# grissom.net
KiCad netlist of a schematic drawn in EAGLE
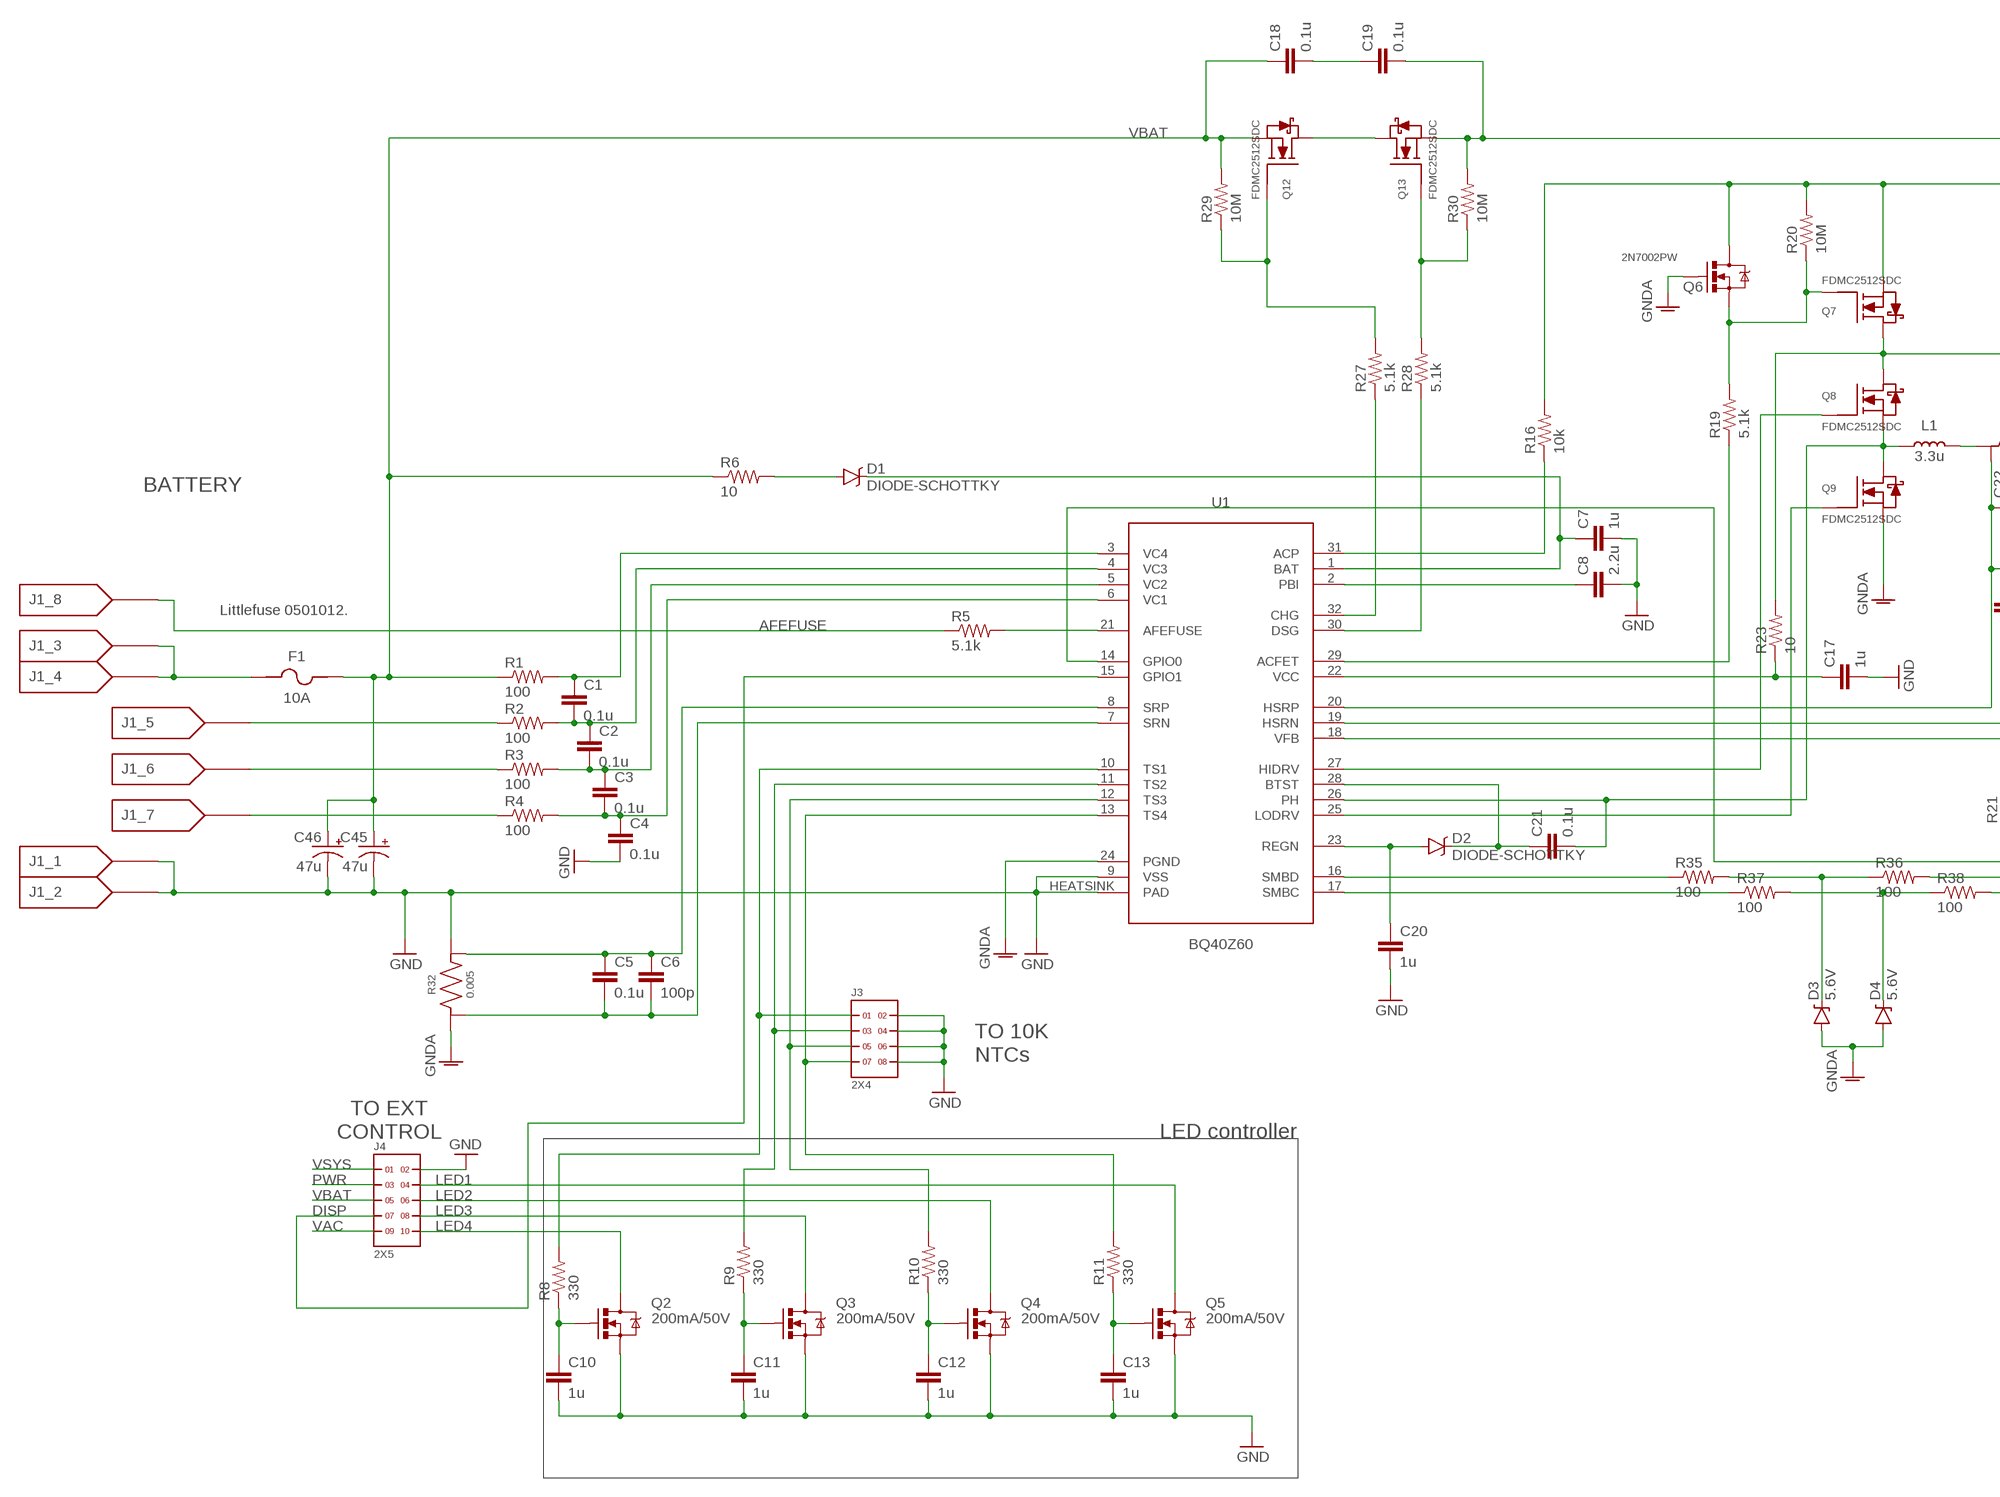
[diagram p0: schematic, sheet 1, part 1 of 2]
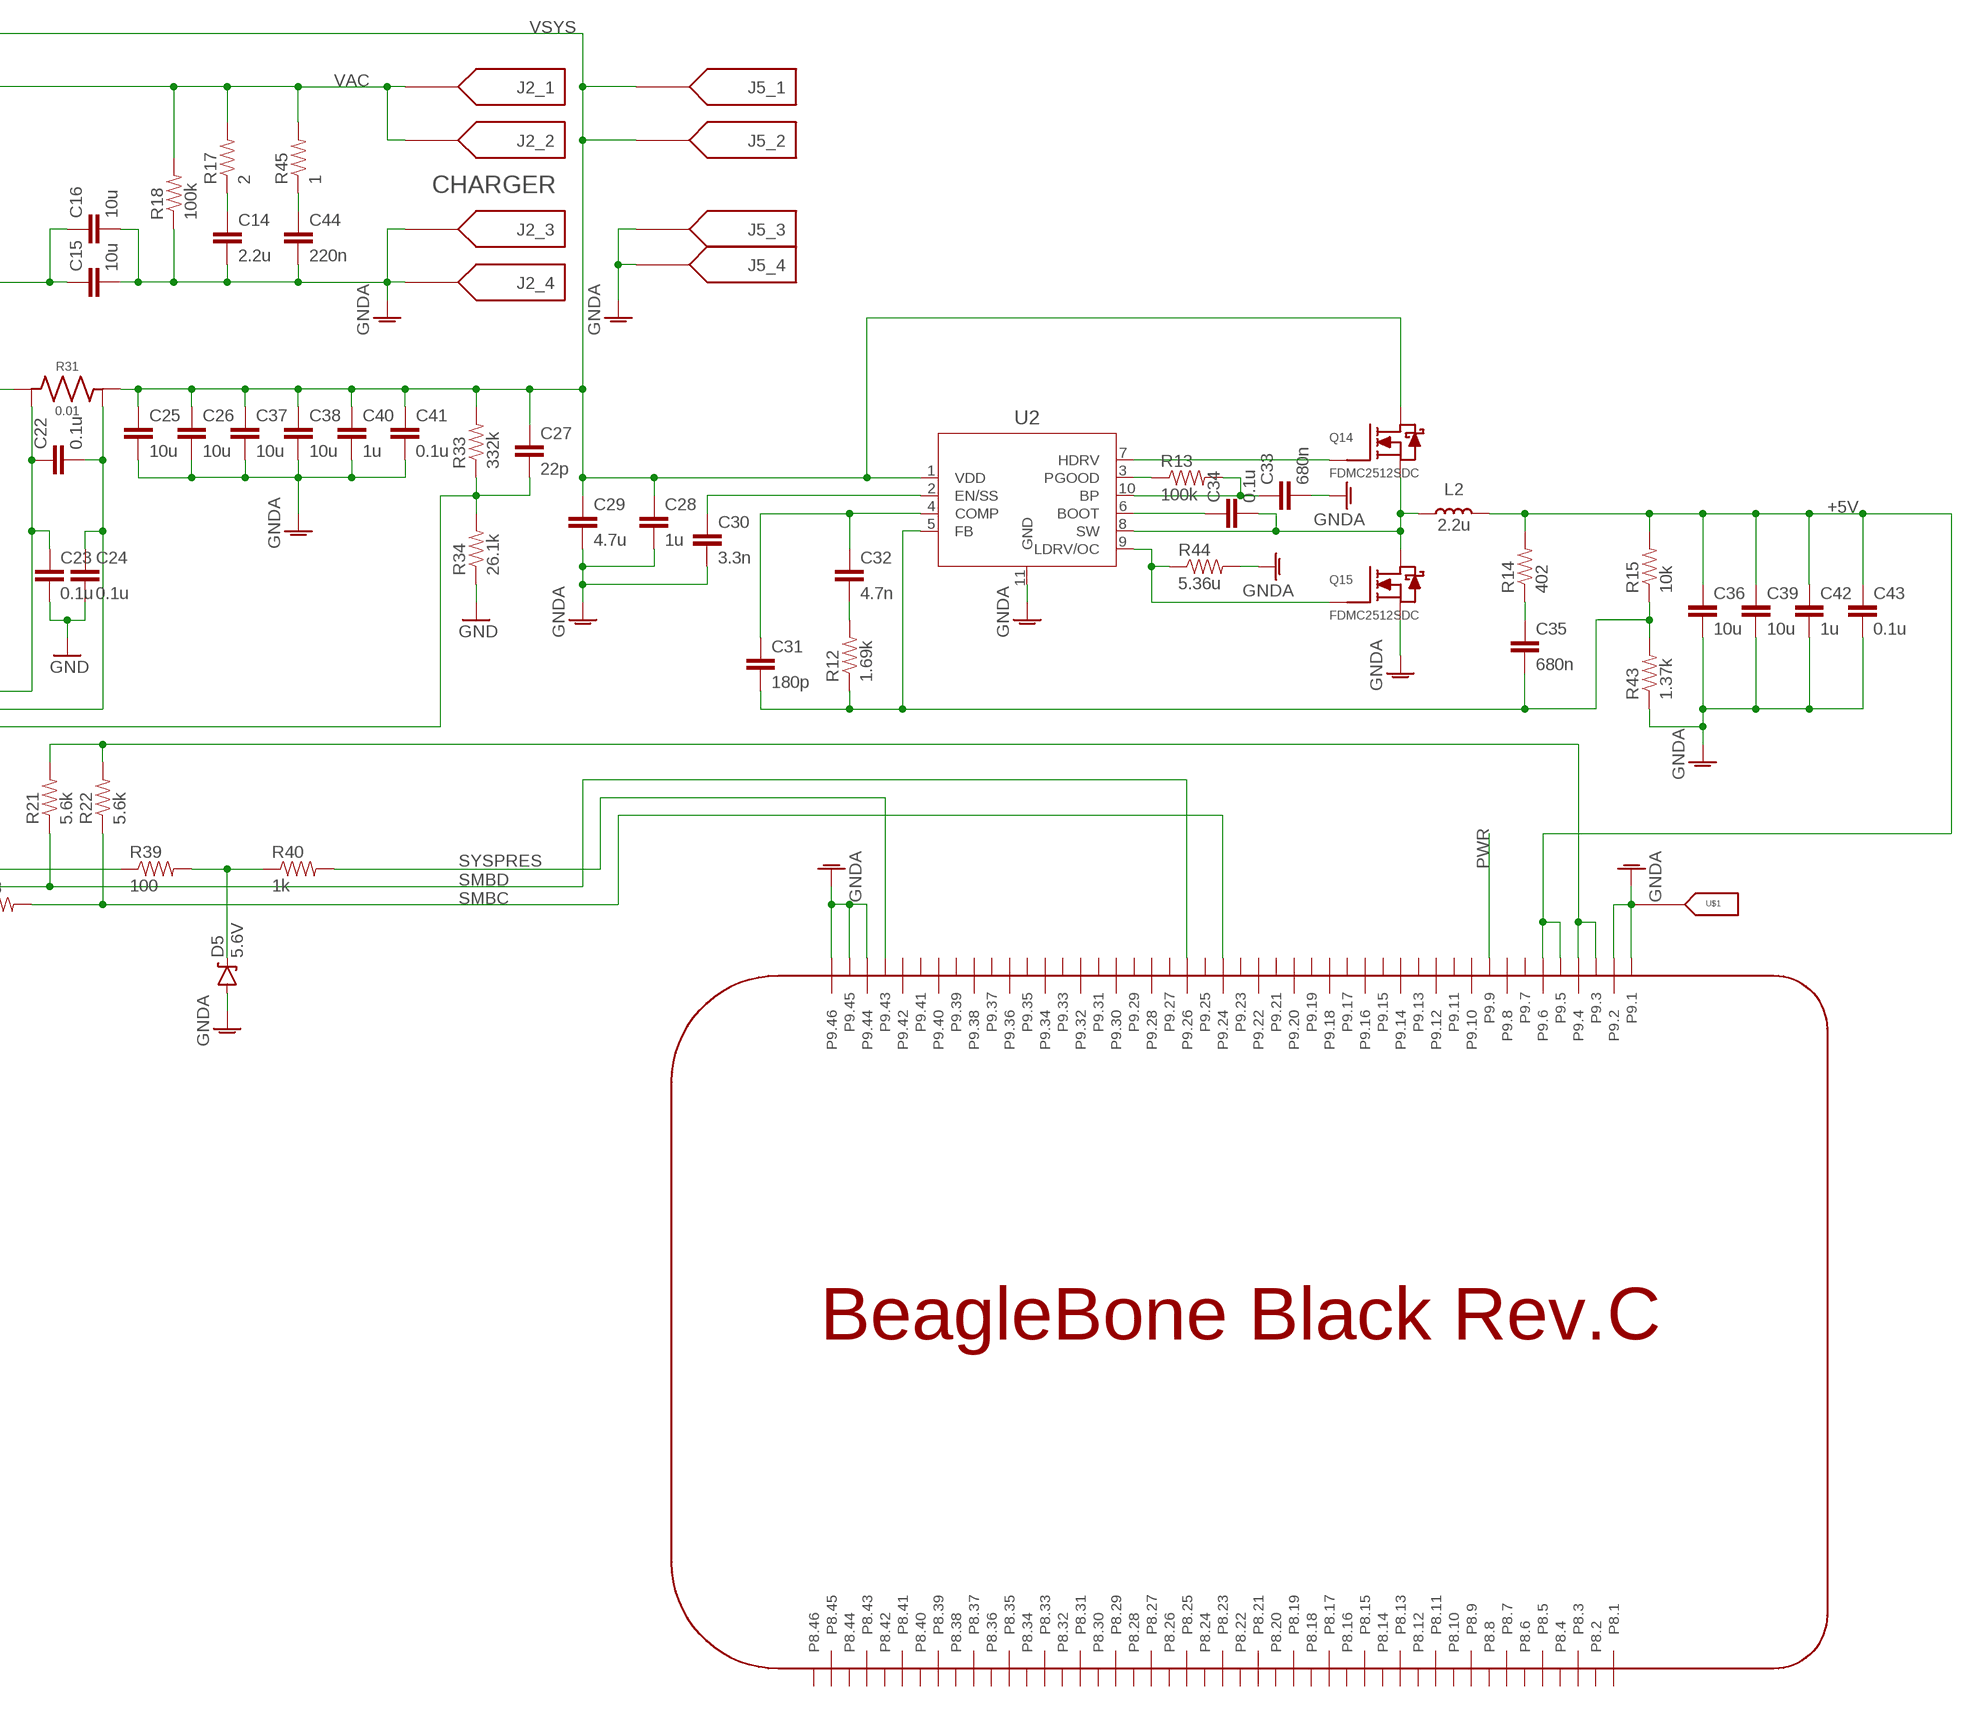
[diagram p1: schematic, sheet 1, part 2 of 2]

(export (version "E")
  (design (tool "Eeschema 10.0.6"))
  (components
    (comp (ref "C1")
      (value "0.1u")
      (footprint "eagle-import:0805")
      (libsource (lib "eagle-import") (part "CAP0805"))
    )
    (comp (ref "C2")
      (value "0.1u")
      (footprint "eagle-import:0805")
      (libsource (lib "eagle-import") (part "CAP0805"))
    )
    (comp (ref "C3")
      (value "0.1u")
      (footprint "eagle-import:0805")
      (libsource (lib "eagle-import") (part "CAP0805"))
    )
    (comp (ref "C4")
      (value "0.1u")
      (footprint "eagle-import:0805")
      (libsource (lib "eagle-import") (part "CAP0805"))
    )
    (comp (ref "C5")
      (value "0.1u")
      (footprint "eagle-import:0805")
      (libsource (lib "eagle-import") (part "CAP0805"))
    )
    (comp (ref "C6")
      (value "100p")
      (footprint "eagle-import:0805")
      (libsource (lib "eagle-import") (part "CAP0805"))
    )
    (comp (ref "C7")
      (value "1u")
      (footprint "eagle-import:0805")
      (libsource (lib "eagle-import") (part "CAP0805"))
    )
    (comp (ref "C8")
      (value "2.2u")
      (footprint "eagle-import:0805")
      (libsource (lib "eagle-import") (part "CAP0805"))
    )
    (comp (ref "C10")
      (value "1u")
      (footprint "eagle-import:0805")
      (libsource (lib "eagle-import") (part "CAP0805"))
    )
    (comp (ref "C11")
      (value "1u")
      (footprint "eagle-import:0805")
      (libsource (lib "eagle-import") (part "CAP0805"))
    )
    (comp (ref "C12")
      (value "1u")
      (footprint "eagle-import:0805")
      (libsource (lib "eagle-import") (part "CAP0805"))
    )
    (comp (ref "C13")
      (value "1u")
      (footprint "eagle-import:0805")
      (libsource (lib "eagle-import") (part "CAP0805"))
    )
    (comp (ref "C14")
      (value "2.2u")
      (footprint "eagle-import:0805")
      (libsource (lib "eagle-import") (part "CAP0805"))
    )
    (comp (ref "C15")
      (value "10u")
      (footprint "eagle-import:1206")
      (libsource (lib "eagle-import") (part "CAP1206"))
    )
    (comp (ref "C16")
      (value "10u")
      (footprint "eagle-import:1206")
      (libsource (lib "eagle-import") (part "CAP1206"))
    )
    (comp (ref "C17")
      (value "1u")
      (footprint "eagle-import:0805")
      (libsource (lib "eagle-import") (part "CAP0805"))
    )
    (comp (ref "C18")
      (value "0.1u")
      (footprint "eagle-import:0805")
      (libsource (lib "eagle-import") (part "CAP0805"))
    )
    (comp (ref "C19")
      (value "0.1u")
      (footprint "eagle-import:0805")
      (libsource (lib "eagle-import") (part "CAP0805"))
    )
    (comp (ref "C20")
      (value "1u")
      (footprint "eagle-import:0805")
      (libsource (lib "eagle-import") (part "CAP0805"))
    )
    (comp (ref "C21")
      (value "0.1u")
      (footprint "eagle-import:0805")
      (libsource (lib "eagle-import") (part "CAP0805"))
    )
    (comp (ref "C22")
      (value "0.1u")
      (footprint "eagle-import:0805")
      (libsource (lib "eagle-import") (part "CAP0805"))
    )
    (comp (ref "C23")
      (value "0.1u")
      (footprint "eagle-import:0805")
      (libsource (lib "eagle-import") (part "CAP0805"))
    )
    (comp (ref "C24")
      (value "0.1u")
      (footprint "eagle-import:0805")
      (libsource (lib "eagle-import") (part "CAP0805"))
    )
    (comp (ref "C25")
      (value "10u")
      (footprint "eagle-import:1206")
      (libsource (lib "eagle-import") (part "CAP1206"))
    )
    (comp (ref "C26")
      (value "10u")
      (footprint "eagle-import:1206")
      (libsource (lib "eagle-import") (part "CAP1206"))
    )
    (comp (ref "C27")
      (value "22p")
      (footprint "eagle-import:0805")
      (libsource (lib "eagle-import") (part "CAP0805"))
    )
    (comp (ref "C28")
      (value "1u")
      (footprint "eagle-import:0805")
      (libsource (lib "eagle-import") (part "CAP0805"))
    )
    (comp (ref "C29")
      (value "4.7u")
      (footprint "eagle-import:0805")
      (libsource (lib "eagle-import") (part "CAP0805"))
    )
    (comp (ref "C30")
      (value "3.3n")
      (footprint "eagle-import:0805")
      (libsource (lib "eagle-import") (part "CAP0805"))
    )
    (comp (ref "C31")
      (value "180p")
      (footprint "eagle-import:0805")
      (libsource (lib "eagle-import") (part "CAP0805"))
    )
    (comp (ref "C32")
      (value "4.7n")
      (footprint "eagle-import:0805")
      (libsource (lib "eagle-import") (part "CAP0805"))
    )
    (comp (ref "C33")
      (value "680n")
      (footprint "eagle-import:0805")
      (libsource (lib "eagle-import") (part "CAP0805"))
    )
    (comp (ref "C34")
      (value "0.1u")
      (footprint "eagle-import:0805")
      (libsource (lib "eagle-import") (part "CAP0805"))
    )
    (comp (ref "C35")
      (value "680n")
      (footprint "eagle-import:0805")
      (libsource (lib "eagle-import") (part "CAP0805"))
    )
    (comp (ref "C36")
      (value "10u")
      (footprint "eagle-import:1206")
      (libsource (lib "eagle-import") (part "CAP1206"))
    )
    (comp (ref "C37")
      (value "10u")
      (footprint "eagle-import:1206")
      (libsource (lib "eagle-import") (part "CAP1206"))
    )
    (comp (ref "C38")
      (value "10u")
      (footprint "eagle-import:1206")
      (libsource (lib "eagle-import") (part "CAP1206"))
    )
    (comp (ref "C39")
      (value "10u")
      (footprint "eagle-import:1206")
      (libsource (lib "eagle-import") (part "CAP1206"))
    )
    (comp (ref "C40")
      (value "1u")
      (footprint "eagle-import:1206")
      (libsource (lib "eagle-import") (part "CAP1206"))
    )
    (comp (ref "C41")
      (value "0.1u")
      (footprint "eagle-import:1206")
      (libsource (lib "eagle-import") (part "CAP1206"))
    )
    (comp (ref "C42")
      (value "1u")
      (footprint "eagle-import:1206")
      (libsource (lib "eagle-import") (part "CAP1206"))
    )
    (comp (ref "C43")
      (value "0.1u")
      (footprint "eagle-import:1206")
      (libsource (lib "eagle-import") (part "CAP1206"))
    )
    (comp (ref "C44")
      (value "220n")
      (footprint "eagle-import:0805")
      (libsource (lib "eagle-import") (part "CAP0805"))
    )
    (comp (ref "C45")
      (value "47u")
      (footprint "eagle-import:CPOL-RADIAL-10UF-25V")
      (libsource (lib "eagle-import") (part "CAP_POLPTH2"))
    )
    (comp (ref "C46")
      (value "47u")
      (footprint "eagle-import:CPOL-RADIAL-10UF-25V")
      (libsource (lib "eagle-import") (part "CAP_POLPTH2"))
    )
    (comp (ref "D1")
      (value "DIODE-SCHOTTKY")
      (footprint "eagle-import:SOT23-3")
      (libsource (lib "eagle-import") (part "DIODE-SCHOTTKY"))
    )
    (comp (ref "D2")
      (value "DIODE-SCHOTTKY")
      (footprint "eagle-import:SOT23-3")
      (libsource (lib "eagle-import") (part "DIODE-SCHOTTKY"))
    )
    (comp (ref "D3")
      (value "5.6V")
      (footprint "eagle-import:SOD-323")
      (libsource (lib "eagle-import") (part "DIODE-ZENER5.6V"))
    )
    (comp (ref "D4")
      (value "5.6V")
      (footprint "eagle-import:SOD-323")
      (libsource (lib "eagle-import") (part "DIODE-ZENER5.6V"))
    )
    (comp (ref "D5")
      (value "5.6V")
      (footprint "eagle-import:SOD-323")
      (libsource (lib "eagle-import") (part "DIODE-ZENER5.6V"))
    )
    (comp (ref "F1")
      (value "10A")
      (footprint "eagle-import:LITTELFUSE_501")
      (libsource (lib "eagle-import") (part "LITTELFUSE_501"))
    )
    (comp (ref "J1")
      (value "105314-X208")
      (footprint "eagle-import:105314-X208")
      (libsource (lib "eagle-import") (part "105314-X208"))
    )
    (comp (ref "J2")
      (value "105314-X204")
      (footprint "eagle-import:105314-X204")
      (libsource (lib "eagle-import") (part "105314-X204"))
    )
    (comp (ref "J3")
      (value "2X4")
      (footprint "eagle-import:2X4")
      (libsource (lib "eagle-import") (part "2X4"))
    )
    (comp (ref "J4")
      (value "2X5")
      (footprint "eagle-import:2X5")
      (libsource (lib "eagle-import") (part "2X5"))
    )
    (comp (ref "J5")
      (value "105314-X204")
      (footprint "eagle-import:105314-X204")
      (libsource (lib "eagle-import") (part "105314-X204"))
    )
    (comp (ref "L1")
      (value "3.3u")
      (footprint "eagle-import:BOURNS_SRP7028A")
      (libsource (lib "eagle-import") (part "BOURNS_SRP7028A"))
    )
    (comp (ref "L2")
      (value "2.2u")
      (footprint "eagle-import:BOURNS_SRP7028A")
      (libsource (lib "eagle-import") (part "BOURNS_SRP7028A"))
    )
    (comp (ref "PCB1")
      (value "BEAGLEBONE_BLACK_BLANK")
      (footprint "eagle-import:BEAGLEBONE_BLACK_BLANK")
      (libsource (lib "eagle-import") (part "BEAGLEBONE_BLACK_BLANK"))
    )
    (comp (ref "Q2")
      (value "200mA/50V")
      (footprint "eagle-import:SOT23-3")
      (libsource (lib "eagle-import") (part "MOSFET-NCHANNELBSS138"))
    )
    (comp (ref "Q3")
      (value "200mA/50V")
      (footprint "eagle-import:SOT23-3")
      (libsource (lib "eagle-import") (part "MOSFET-NCHANNELBSS138"))
    )
    (comp (ref "Q4")
      (value "200mA/50V")
      (footprint "eagle-import:SOT23-3")
      (libsource (lib "eagle-import") (part "MOSFET-NCHANNELBSS138"))
    )
    (comp (ref "Q5")
      (value "200mA/50V")
      (footprint "eagle-import:SOT23-3")
      (libsource (lib "eagle-import") (part "MOSFET-NCHANNELBSS138"))
    )
    (comp (ref "Q6")
      (value "2N7002PW")
      (footprint "eagle-import:SOT323")
      (libsource (lib "eagle-import") (part "MOSFET-NCHANNEL2N7002PW"))
    )
    (comp (ref "Q7")
      (value "FDMC2512SDC")
      (footprint "eagle-import:MO240")
      (libsource (lib "eagle-import") (part "FDMC2512SDC"))
    )
    (comp (ref "Q8")
      (value "FDMC2512SDC")
      (footprint "eagle-import:MO240")
      (libsource (lib "eagle-import") (part "FDMC2512SDC"))
    )
    (comp (ref "Q9")
      (value "FDMC2512SDC")
      (footprint "eagle-import:MO240")
      (libsource (lib "eagle-import") (part "FDMC2512SDC"))
    )
    (comp (ref "Q12")
      (value "FDMC2512SDC")
      (footprint "eagle-import:MO240")
      (libsource (lib "eagle-import") (part "FDMC2512SDC"))
    )
    (comp (ref "Q13")
      (value "FDMC2512SDC")
      (footprint "eagle-import:MO240")
      (libsource (lib "eagle-import") (part "FDMC2512SDC"))
    )
    (comp (ref "Q14")
      (value "FDMC2512SDC")
      (footprint "eagle-import:MO240")
      (libsource (lib "eagle-import") (part "FDMC2512SDC"))
    )
    (comp (ref "Q15")
      (value "FDMC2512SDC")
      (footprint "eagle-import:MO240")
      (libsource (lib "eagle-import") (part "FDMC2512SDC"))
    )
    (comp (ref "R1")
      (value "100")
      (footprint "eagle-import:0805")
      (libsource (lib "eagle-import") (part "RESISTOR0805-RES"))
    )
    (comp (ref "R2")
      (value "100")
      (footprint "eagle-import:0805")
      (libsource (lib "eagle-import") (part "RESISTOR0805-RES"))
    )
    (comp (ref "R3")
      (value "100")
      (footprint "eagle-import:0805")
      (libsource (lib "eagle-import") (part "RESISTOR0805-RES"))
    )
    (comp (ref "R4")
      (value "100")
      (footprint "eagle-import:0805")
      (libsource (lib "eagle-import") (part "RESISTOR0805-RES"))
    )
    (comp (ref "R5")
      (value "5.1k")
      (footprint "eagle-import:0805")
      (libsource (lib "eagle-import") (part "RESISTOR0805-RES"))
    )
    (comp (ref "R6")
      (value "10")
      (footprint "eagle-import:1206")
      (libsource (lib "eagle-import") (part "RESISTOR1206"))
    )
    (comp (ref "R8")
      (value "330")
      (footprint "eagle-import:0805")
      (libsource (lib "eagle-import") (part "RESISTOR0805-RES"))
    )
    (comp (ref "R9")
      (value "330")
      (footprint "eagle-import:0805")
      (libsource (lib "eagle-import") (part "RESISTOR0805-RES"))
    )
    (comp (ref "R10")
      (value "330")
      (footprint "eagle-import:0805")
      (libsource (lib "eagle-import") (part "RESISTOR0805-RES"))
    )
    (comp (ref "R11")
      (value "330")
      (footprint "eagle-import:0805")
      (libsource (lib "eagle-import") (part "RESISTOR0805-RES"))
    )
    (comp (ref "R12")
      (value "1.69k")
      (footprint "eagle-import:0805")
      (libsource (lib "eagle-import") (part "RESISTOR0805-RES"))
    )
    (comp (ref "R13")
      (value "100k")
      (footprint "eagle-import:0805")
      (libsource (lib "eagle-import") (part "RESISTOR0805-RES"))
    )
    (comp (ref "R14")
      (value "402")
      (footprint "eagle-import:0805")
      (libsource (lib "eagle-import") (part "RESISTOR0805-RES"))
    )
    (comp (ref "R15")
      (value "10k")
      (footprint "eagle-import:0805")
      (libsource (lib "eagle-import") (part "RESISTOR0805-RES"))
    )
    (comp (ref "R16")
      (value "10k")
      (footprint "eagle-import:0805")
      (libsource (lib "eagle-import") (part "RESISTOR0805-RES"))
    )
    (comp (ref "R17")
      (value "2")
      (footprint "eagle-import:0805")
      (libsource (lib "eagle-import") (part "RESISTOR0805-RES"))
    )
    (comp (ref "R18")
      (value "100k")
      (footprint "eagle-import:0805")
      (libsource (lib "eagle-import") (part "RESISTOR0805-RES"))
    )
    (comp (ref "R19")
      (value "5.1k")
      (footprint "eagle-import:0805")
      (libsource (lib "eagle-import") (part "RESISTOR0805-RES"))
    )
    (comp (ref "R20")
      (value "10M")
      (footprint "eagle-import:0805")
      (libsource (lib "eagle-import") (part "RESISTOR0805-RES"))
    )
    (comp (ref "R21")
      (value "5.6k")
      (footprint "eagle-import:0805")
      (libsource (lib "eagle-import") (part "RESISTOR0805-RES"))
    )
    (comp (ref "R22")
      (value "5.6k")
      (footprint "eagle-import:0805")
      (libsource (lib "eagle-import") (part "RESISTOR0805-RES"))
    )
    (comp (ref "R23")
      (value "10")
      (footprint "eagle-import:0805")
      (libsource (lib "eagle-import") (part "RESISTOR0805-RES"))
    )
    (comp (ref "R27")
      (value "5.1k")
      (footprint "eagle-import:0805")
      (libsource (lib "eagle-import") (part "RESISTOR0805-RES"))
    )
    (comp (ref "R28")
      (value "5.1k")
      (footprint "eagle-import:0805")
      (libsource (lib "eagle-import") (part "RESISTOR0805-RES"))
    )
    (comp (ref "R29")
      (value "10M")
      (footprint "eagle-import:0805")
      (libsource (lib "eagle-import") (part "RESISTOR0805-RES"))
    )
    (comp (ref "R30")
      (value "10M")
      (footprint "eagle-import:0805")
      (libsource (lib "eagle-import") (part "RESISTOR0805-RES"))
    )
    (comp (ref "R31")
      (value "0.01")
      (footprint "eagle-import:1206_4T")
      (libsource (lib "eagle-import") (part "OHMITE_FC4L32"))
    )
    (comp (ref "R32")
      (value "0.005")
      (footprint "eagle-import:0612_4T")
      (libsource (lib "eagle-import") (part "VISHAY_WSK0612"))
    )
    (comp (ref "R33")
      (value "332k")
      (footprint "eagle-import:0805")
      (libsource (lib "eagle-import") (part "RESISTOR0805-RES"))
    )
    (comp (ref "R34")
      (value "26.1k")
      (footprint "eagle-import:0805")
      (libsource (lib "eagle-import") (part "RESISTOR0805-RES"))
    )
    (comp (ref "R35")
      (value "100")
      (footprint "eagle-import:0805")
      (libsource (lib "eagle-import") (part "RESISTOR0805-RES"))
    )
    (comp (ref "R36")
      (value "100")
      (footprint "eagle-import:0805")
      (libsource (lib "eagle-import") (part "RESISTOR0805-RES"))
    )
    (comp (ref "R37")
      (value "100")
      (footprint "eagle-import:0805")
      (libsource (lib "eagle-import") (part "RESISTOR0805-RES"))
    )
    (comp (ref "R38")
      (value "100")
      (footprint "eagle-import:0805")
      (libsource (lib "eagle-import") (part "RESISTOR0805-RES"))
    )
    (comp (ref "R39")
      (value "100")
      (footprint "eagle-import:0805")
      (libsource (lib "eagle-import") (part "RESISTOR0805-RES"))
    )
    (comp (ref "R40")
      (value "1k")
      (footprint "eagle-import:0805")
      (libsource (lib "eagle-import") (part "RESISTOR0805-RES"))
    )
    (comp (ref "R43")
      (value "1.37k")
      (footprint "eagle-import:0805")
      (libsource (lib "eagle-import") (part "RESISTOR0805-RES"))
    )
    (comp (ref "R44")
      (value "5.36u")
      (footprint "eagle-import:0805")
      (libsource (lib "eagle-import") (part "RESISTOR0805-RES"))
    )
    (comp (ref "R45")
      (value "1")
      (footprint "eagle-import:0805")
      (libsource (lib "eagle-import") (part "RESISTOR0805-RES"))
    )
    (comp (ref "U$1")
      (value "SU_LOGO-DUMMY2")
      (footprint "eagle-import:SU_LOGO_SS")
      (libsource (lib "eagle-import") (part "SU_LOGO-DUMMY2"))
    )
    (comp (ref "U1")
      (value "BQ40Z60")
      (footprint "eagle-import:QFN32")
      (libsource (lib "eagle-import") (part "BQ40Z60"))
    )
    (comp (ref "U2")
      (value "TPS40305DRCR")
      (footprint "eagle-import:S-PVSON-N10")
      (libsource (lib "eagle-import") (part "TPS40305DRCR"))
    )
  )
  (nets
    (net (code "1") (name "/+5V") (class "Default")
      (node (ref "C36") (pin "1") (pinfunction "1_1") (pintype "passive"))
      (node (ref "C39") (pin "1") (pinfunction "1_1") (pintype "passive"))
      (node (ref "C42") (pin "1") (pinfunction "1_1") (pintype "passive"))
      (node (ref "C43") (pin "1") (pinfunction "1_1") (pintype "passive"))
      (node (ref "L2") (pin "P$2") (pinfunction "P$2_P$2") (pintype "bidirectional"))
      (node (ref "PCB1") (pin "P9.5") (pinfunction "P9.5_P9.5") (pintype "bidirectional"))
      (node (ref "PCB1") (pin "P9.6") (pinfunction "P9.6_P9.6") (pintype "bidirectional"))
      (node (ref "R14") (pin "2") (pinfunction "2_2") (pintype "passive"))
      (node (ref "R15") (pin "2") (pinfunction "2_2") (pintype "passive"))
    )
    (net (code "2") (name "/AFEFUSE") (class "Default")
      (node (ref "J1") (pin "P$8") (pinfunction "P$1_P$8") (pintype "bidirectional"))
      (node (ref "R5") (pin "1") (pinfunction "1_1") (pintype "passive"))
    )
    (net (code "3") (name "/DISP") (class "Default")
      (node (ref "J4") (pin "7") (pinfunction "7_7") (pintype "bidirectional"))
      (node (ref "U1") (pin "15") (pinfunction "GPIO1_15") (pintype "bidirectional"))
    )
    (net (code "4") (name "/LED1") (class "Default")
      (node (ref "J4") (pin "4") (pinfunction "4_4") (pintype "bidirectional"))
      (node (ref "Q5") (pin "3") (pinfunction "D_3") (pintype "passive"))
    )
    (net (code "5") (name "/LED2") (class "Default")
      (node (ref "J4") (pin "6") (pinfunction "6_6") (pintype "bidirectional"))
      (node (ref "Q4") (pin "3") (pinfunction "D_3") (pintype "passive"))
    )
    (net (code "6") (name "/LED3") (class "Default")
      (node (ref "J4") (pin "8") (pinfunction "8_8") (pintype "bidirectional"))
      (node (ref "Q3") (pin "3") (pinfunction "D_3") (pintype "passive"))
    )
    (net (code "7") (name "/LED4") (class "Default")
      (node (ref "J4") (pin "10") (pinfunction "10_10") (pintype "bidirectional"))
      (node (ref "Q2") (pin "3") (pinfunction "D_3") (pintype "passive"))
    )
    (net (code "8") (name "/PWR") (class "Default")
      (node (ref "J4") (pin "3") (pinfunction "3_3") (pintype "bidirectional"))
      (node (ref "PCB1") (pin "P9.9") (pinfunction "P9.9_P9.9") (pintype "bidirectional"))
    )
    (net (code "9") (name "/VAC") (class "Default")
      (node (ref "J2") (pin "P$1") (pinfunction "P$1_P$1") (pintype "bidirectional"))
      (node (ref "J2") (pin "P$2") (pinfunction "P$1_P$2") (pintype "bidirectional"))
      (node (ref "J4") (pin "9") (pinfunction "9_9") (pintype "bidirectional"))
      (node (ref "Q6") (pin "3") (pinfunction "D_3") (pintype "passive"))
      (node (ref "Q7") (pin "P$1") (pinfunction "S_P$1") (pintype "bidirectional"))
      (node (ref "Q7") (pin "P$2") (pinfunction "S_P$2") (pintype "bidirectional"))
      (node (ref "Q7") (pin "P$3") (pinfunction "S_P$3") (pintype "bidirectional"))
      (node (ref "R16") (pin "2") (pinfunction "2_2") (pintype "passive"))
      (node (ref "R17") (pin "2") (pinfunction "2_2") (pintype "passive"))
      (node (ref "R18") (pin "2") (pinfunction "2_2") (pintype "passive"))
      (node (ref "R20") (pin "2") (pinfunction "2_2") (pintype "passive"))
      (node (ref "R45") (pin "2") (pinfunction "2_2") (pintype "passive"))
    )
    (net (code "10") (name "/VBAT") (class "Default")
      (node (ref "C18") (pin "1") (pinfunction "1_1") (pintype "passive"))
      (node (ref "C45") (pin "1") (pinfunction "+_1") (pintype "passive"))
      (node (ref "C46") (pin "1") (pinfunction "+_1") (pintype "passive"))
      (node (ref "F1") (pin "P$2") (pinfunction "P$2_P$2") (pintype "bidirectional"))
      (node (ref "J4") (pin "5") (pinfunction "5_5") (pintype "bidirectional"))
      (node (ref "Q12") (pin "P$1") (pinfunction "S_P$1") (pintype "bidirectional"))
      (node (ref "Q12") (pin "P$2") (pinfunction "S_P$2") (pintype "bidirectional"))
      (node (ref "Q12") (pin "P$3") (pinfunction "S_P$3") (pintype "bidirectional"))
      (node (ref "R1") (pin "1") (pinfunction "1_1") (pintype "passive"))
      (node (ref "R29") (pin "2") (pinfunction "2_2") (pintype "passive"))
      (node (ref "R6") (pin "1") (pinfunction "1_1") (pintype "passive"))
    )
    (net (code "11") (name "/VSYS") (class "Default")
      (node (ref "C19") (pin "2") (pinfunction "2_2") (pintype "passive"))
      (node (ref "C25") (pin "1") (pinfunction "1_1") (pintype "passive"))
      (node (ref "C26") (pin "1") (pinfunction "1_1") (pintype "passive"))
      (node (ref "C27") (pin "1") (pinfunction "1_1") (pintype "passive"))
      (node (ref "C28") (pin "1") (pinfunction "1_1") (pintype "passive"))
      (node (ref "C29") (pin "1") (pinfunction "1_1") (pintype "passive"))
      (node (ref "C37") (pin "1") (pinfunction "1_1") (pintype "passive"))
      (node (ref "C38") (pin "1") (pinfunction "1_1") (pintype "passive"))
      (node (ref "C40") (pin "1") (pinfunction "1_1") (pintype "passive"))
      (node (ref "C41") (pin "1") (pinfunction "1_1") (pintype "passive"))
      (node (ref "J4") (pin "1") (pinfunction "1_1") (pintype "bidirectional"))
      (node (ref "J5") (pin "P$1") (pinfunction "P$1_P$1") (pintype "bidirectional"))
      (node (ref "J5") (pin "P$2") (pinfunction "P$1_P$2") (pintype "bidirectional"))
      (node (ref "Q13") (pin "P$1") (pinfunction "S_P$1") (pintype "bidirectional"))
      (node (ref "Q13") (pin "P$2") (pinfunction "S_P$2") (pintype "bidirectional"))
      (node (ref "Q13") (pin "P$3") (pinfunction "S_P$3") (pintype "bidirectional"))
      (node (ref "Q14") (pin "P$5") (pinfunction "D_P$5") (pintype "bidirectional"))
      (node (ref "Q14") (pin "P$6") (pinfunction "D_P$6") (pintype "bidirectional"))
      (node (ref "Q14") (pin "P$7") (pinfunction "D_P$7") (pintype "bidirectional"))
      (node (ref "Q14") (pin "P$8") (pinfunction "D_P$8") (pintype "bidirectional"))
      (node (ref "Q14") (pin "PAD") (pinfunction "D_PAD") (pintype "bidirectional"))
      (node (ref "R30") (pin "2") (pinfunction "2_2") (pintype "passive"))
      (node (ref "R31") (pin "P$2") (pinfunction "P$2_P$2") (pintype "bidirectional"))
      (node (ref "R33") (pin "2") (pinfunction "2_2") (pintype "passive"))
      (node (ref "U2") (pin "1") (pinfunction "VDD_1") (pintype "passive"))
    )
    (net (code "12") (name "GND") (class "Default")
      (node (ref "C10") (pin "2") (pinfunction "2_2") (pintype "passive"))
      (node (ref "C11") (pin "2") (pinfunction "2_2") (pintype "passive"))
      (node (ref "C12") (pin "2") (pinfunction "2_2") (pintype "passive"))
      (node (ref "C13") (pin "2") (pinfunction "2_2") (pintype "passive"))
      (node (ref "C17") (pin "2") (pinfunction "2_2") (pintype "passive"))
      (node (ref "C20") (pin "2") (pinfunction "2_2") (pintype "passive"))
      (node (ref "C23") (pin "2") (pinfunction "2_2") (pintype "passive"))
      (node (ref "C24") (pin "2") (pinfunction "2_2") (pintype "passive"))
      (node (ref "C4") (pin "2") (pinfunction "2_2") (pintype "passive"))
      (node (ref "C45") (pin "2") (pinfunction "-_2") (pintype "passive"))
      (node (ref "C46") (pin "2") (pinfunction "-_2") (pintype "passive"))
      (node (ref "C7") (pin "2") (pinfunction "2_2") (pintype "passive"))
      (node (ref "C8") (pin "2") (pinfunction "2_2") (pintype "passive"))
      (node (ref "J1") (pin "P$1") (pinfunction "P$1_P$1") (pintype "bidirectional"))
      (node (ref "J1") (pin "P$2") (pinfunction "P$1_P$2") (pintype "bidirectional"))
      (node (ref "J3") (pin "2") (pinfunction "2_2") (pintype "bidirectional"))
      (node (ref "J3") (pin "4") (pinfunction "4_4") (pintype "bidirectional"))
      (node (ref "J3") (pin "6") (pinfunction "6_6") (pintype "bidirectional"))
      (node (ref "J3") (pin "8") (pinfunction "8_8") (pintype "bidirectional"))
      (node (ref "J4") (pin "2") (pinfunction "2_2") (pintype "bidirectional"))
      (node (ref "Q2") (pin "2") (pinfunction "S_2") (pintype "passive"))
      (node (ref "Q3") (pin "2") (pinfunction "S_2") (pintype "passive"))
      (node (ref "Q4") (pin "2") (pinfunction "S_2") (pintype "passive"))
      (node (ref "Q5") (pin "2") (pinfunction "S_2") (pintype "passive"))
      (node (ref "R32") (pin "P$2") (pinfunction "P$2_P$2") (pintype "bidirectional"))
      (node (ref "R34") (pin "1") (pinfunction "1_1") (pintype "passive"))
      (node (ref "U1") (pin "9") (pinfunction "VSS_9") (pintype "bidirectional"))
      (node (ref "U1") (pin "HEATSINK") (pinfunction "PAD_HEATSINK") (pintype "bidirectional"))
    )
    (net (code "13") (name "GNDA") (class "Default")
      (node (ref "C14") (pin "2") (pinfunction "2_2") (pintype "passive"))
      (node (ref "C15") (pin "2") (pinfunction "2_2") (pintype "passive"))
      (node (ref "C16") (pin "2") (pinfunction "2_2") (pintype "passive"))
      (node (ref "C25") (pin "2") (pinfunction "2_2") (pintype "passive"))
      (node (ref "C26") (pin "2") (pinfunction "2_2") (pintype "passive"))
      (node (ref "C28") (pin "2") (pinfunction "2_2") (pintype "passive"))
      (node (ref "C29") (pin "2") (pinfunction "2_2") (pintype "passive"))
      (node (ref "C30") (pin "2") (pinfunction "2_2") (pintype "passive"))
      (node (ref "C33") (pin "2") (pinfunction "2_2") (pintype "passive"))
      (node (ref "C36") (pin "2") (pinfunction "2_2") (pintype "passive"))
      (node (ref "C37") (pin "2") (pinfunction "2_2") (pintype "passive"))
      (node (ref "C38") (pin "2") (pinfunction "2_2") (pintype "passive"))
      (node (ref "C39") (pin "2") (pinfunction "2_2") (pintype "passive"))
      (node (ref "C40") (pin "2") (pinfunction "2_2") (pintype "passive"))
      (node (ref "C41") (pin "2") (pinfunction "2_2") (pintype "passive"))
      (node (ref "C42") (pin "2") (pinfunction "2_2") (pintype "passive"))
      (node (ref "C43") (pin "2") (pinfunction "2_2") (pintype "passive"))
      (node (ref "C44") (pin "2") (pinfunction "2_2") (pintype "passive"))
      (node (ref "D3") (pin "A") (pinfunction "A_A") (pintype "passive"))
      (node (ref "D4") (pin "A") (pinfunction "A_A") (pintype "passive"))
      (node (ref "D5") (pin "A") (pinfunction "A_A") (pintype "passive"))
      (node (ref "J2") (pin "P$3") (pinfunction "P$1_P$3") (pintype "bidirectional"))
      (node (ref "J2") (pin "P$4") (pinfunction "P$1_P$4") (pintype "bidirectional"))
      (node (ref "J5") (pin "P$3") (pinfunction "P$1_P$3") (pintype "bidirectional"))
      (node (ref "J5") (pin "P$4") (pinfunction "P$1_P$4") (pintype "bidirectional"))
      (node (ref "PCB1") (pin "P9.1") (pinfunction "P9.1_P9.1") (pintype "bidirectional"))
      (node (ref "PCB1") (pin "P9.2") (pinfunction "P9.2_P9.2") (pintype "bidirectional"))
      (node (ref "PCB1") (pin "P9.44") (pinfunction "P9.44_P9.44") (pintype "bidirectional"))
      (node (ref "PCB1") (pin "P9.45") (pinfunction "P9.45_P9.45") (pintype "bidirectional"))
      (node (ref "PCB1") (pin "P9.46") (pinfunction "P9.46_P9.46") (pintype "bidirectional"))
      (node (ref "Q15") (pin "P$1") (pinfunction "S_P$1") (pintype "bidirectional"))
      (node (ref "Q15") (pin "P$2") (pinfunction "S_P$2") (pintype "bidirectional"))
      (node (ref "Q15") (pin "P$3") (pinfunction "S_P$3") (pintype "bidirectional"))
      (node (ref "Q6") (pin "1") (pinfunction "G_1") (pintype "passive"))
      (node (ref "Q9") (pin "P$1") (pinfunction "S_P$1") (pintype "bidirectional"))
      (node (ref "Q9") (pin "P$2") (pinfunction "S_P$2") (pintype "bidirectional"))
      (node (ref "Q9") (pin "P$3") (pinfunction "S_P$3") (pintype "bidirectional"))
      (node (ref "R18") (pin "1") (pinfunction "1_1") (pintype "passive"))
      (node (ref "R32") (pin "P$1") (pinfunction "P$1_P$1") (pintype "bidirectional"))
      (node (ref "R43") (pin "1") (pinfunction "1_1") (pintype "passive"))
      (node (ref "R44") (pin "2") (pinfunction "2_2") (pintype "passive"))
      (node (ref "U$1") (pin "P$1") (pinfunction "P$1_P$1") (pintype "bidirectional"))
      (node (ref "U1") (pin "24") (pinfunction "PGND_24") (pintype "bidirectional"))
      (node (ref "U2") (pin "11") (pinfunction "GND_11") (pintype "passive"))
    )
    (net (code "14") (name "Net-(C14-Pad1)") (class "Default")
      (node (ref "C14") (pin "1") (pinfunction "1_1") (pintype "passive"))
      (node (ref "R17") (pin "1") (pinfunction "1_1") (pintype "passive"))
    )
    (net (code "15") (name "Net-(C15-Pad1)") (class "Default")
      (node (ref "C15") (pin "1") (pinfunction "1_1") (pintype "passive"))
      (node (ref "C16") (pin "1") (pinfunction "1_1") (pintype "passive"))
      (node (ref "Q7") (pin "P$5") (pinfunction "D_P$5") (pintype "bidirectional"))
      (node (ref "Q7") (pin "P$6") (pinfunction "D_P$6") (pintype "bidirectional"))
      (node (ref "Q7") (pin "P$7") (pinfunction "D_P$7") (pintype "bidirectional"))
      (node (ref "Q7") (pin "P$8") (pinfunction "D_P$8") (pintype "bidirectional"))
      (node (ref "Q7") (pin "PAD") (pinfunction "D_PAD") (pintype "bidirectional"))
      (node (ref "Q8") (pin "P$5") (pinfunction "D_P$5") (pintype "bidirectional"))
      (node (ref "Q8") (pin "P$6") (pinfunction "D_P$6") (pintype "bidirectional"))
      (node (ref "Q8") (pin "P$7") (pinfunction "D_P$7") (pintype "bidirectional"))
      (node (ref "Q8") (pin "P$8") (pinfunction "D_P$8") (pintype "bidirectional"))
      (node (ref "Q8") (pin "PAD") (pinfunction "D_PAD") (pintype "bidirectional"))
      (node (ref "R23") (pin "2") (pinfunction "2_2") (pintype "passive"))
    )
    (net (code "16") (name "Net-(C18-Pad2)") (class "Default")
      (node (ref "C18") (pin "2") (pinfunction "2_2") (pintype "passive"))
      (node (ref "C19") (pin "1") (pinfunction "1_1") (pintype "passive"))
    )
    (net (code "17") (name "Net-(C32-Pad2)") (class "Default")
      (node (ref "C32") (pin "2") (pinfunction "2_2") (pintype "passive"))
      (node (ref "R12") (pin "2") (pinfunction "2_2") (pintype "passive"))
    )
    (net (code "18") (name "Net-(C35-Pad1)") (class "Default")
      (node (ref "C35") (pin "1") (pinfunction "1_1") (pintype "passive"))
      (node (ref "R14") (pin "1") (pinfunction "1_1") (pintype "passive"))
    )
    (net (code "19") (name "Net-(C44-Pad1)") (class "Default")
      (node (ref "C44") (pin "1") (pinfunction "1_1") (pintype "passive"))
      (node (ref "R45") (pin "1") (pinfunction "1_1") (pintype "passive"))
    )
    (net (code "20") (name "Net-(D1-A-Pad1)") (class "Default")
      (node (ref "D1") (pin "1") (pinfunction "A_1") (pintype "passive"))
      (node (ref "D1") (pin "2") (pinfunction "A_2") (pintype "passive"))
      (node (ref "R6") (pin "2") (pinfunction "2_2") (pintype "passive"))
    )
    (net (code "21") (name "Net-(D1-C)") (class "Default")
      (node (ref "C7") (pin "1") (pinfunction "1_1") (pintype "passive"))
      (node (ref "D1") (pin "3") (pinfunction "C_3") (pintype "passive"))
      (node (ref "U1") (pin "1") (pinfunction "BAT_1") (pintype "bidirectional"))
    )
    (net (code "22") (name "Net-(D2-C)") (class "Default")
      (node (ref "C21") (pin "1") (pinfunction "1_1") (pintype "passive"))
      (node (ref "D2") (pin "3") (pinfunction "C_3") (pintype "passive"))
      (node (ref "U1") (pin "28") (pinfunction "BTST_28") (pintype "bidirectional"))
    )
    (net (code "23") (name "Net-(D3-PadC)") (class "Default")
      (node (ref "D3") (pin "C") (pinfunction "C_C") (pintype "passive"))
      (node (ref "R35") (pin "2") (pinfunction "2_2") (pintype "passive"))
      (node (ref "R36") (pin "1") (pinfunction "1_1") (pintype "passive"))
    )
    (net (code "24") (name "Net-(D4-PadC)") (class "Default")
      (node (ref "D4") (pin "C") (pinfunction "C_C") (pintype "passive"))
      (node (ref "R37") (pin "2") (pinfunction "2_2") (pintype "passive"))
      (node (ref "R38") (pin "1") (pinfunction "1_1") (pintype "passive"))
    )
    (net (code "25") (name "Net-(D5-PadC)") (class "Default")
      (node (ref "D5") (pin "C") (pinfunction "C_C") (pintype "passive"))
      (node (ref "R39") (pin "2") (pinfunction "2_2") (pintype "passive"))
      (node (ref "R40") (pin "1") (pinfunction "1_1") (pintype "passive"))
    )
    (net (code "26") (name "Net-(J1C-P$1)") (class "Default")
      (node (ref "F1") (pin "P$1") (pinfunction "P$1_P$1") (pintype "bidirectional"))
      (node (ref "J1") (pin "P$3") (pinfunction "P$1_P$3") (pintype "bidirectional"))
      (node (ref "J1") (pin "P$4") (pinfunction "P$1_P$4") (pintype "bidirectional"))
    )
    (net (code "27") (name "Net-(J1E-P$1)") (class "Default")
      (node (ref "J1") (pin "P$5") (pinfunction "P$1_P$5") (pintype "bidirectional"))
      (node (ref "R2") (pin "1") (pinfunction "1_1") (pintype "passive"))
    )
    (net (code "28") (name "Net-(J1F-P$1)") (class "Default")
      (node (ref "J1") (pin "P$6") (pinfunction "P$1_P$6") (pintype "bidirectional"))
      (node (ref "R3") (pin "1") (pinfunction "1_1") (pintype "passive"))
    )
    (net (code "29") (name "Net-(J1G-P$1)") (class "Default")
      (node (ref "J1") (pin "P$7") (pinfunction "P$1_P$7") (pintype "bidirectional"))
      (node (ref "R4") (pin "1") (pinfunction "1_1") (pintype "passive"))
    )
    (net (code "30") (name "Net-(L1-PadP$2)") (class "Default")
      (node (ref "L1") (pin "P$2") (pinfunction "P$2_P$2") (pintype "bidirectional"))
      (node (ref "R31") (pin "P$1") (pinfunction "P$1_P$1") (pintype "bidirectional"))
    )
    (net (code "31") (name "Net-(PCB1-PadP9.3)") (class "Default")
      (node (ref "PCB1") (pin "P9.3") (pinfunction "P9.3_P9.3") (pintype "bidirectional"))
      (node (ref "PCB1") (pin "P9.4") (pinfunction "P9.4_P9.4") (pintype "bidirectional"))
      (node (ref "R21") (pin "2") (pinfunction "2_2") (pintype "passive"))
      (node (ref "R22") (pin "2") (pinfunction "2_2") (pintype "passive"))
    )
    (net (code "32") (name "Net-(PCB1-PadP9.24)") (class "Default")
      (node (ref "PCB1") (pin "P9.24") (pinfunction "P9.24_P9.24") (pintype "bidirectional"))
      (node (ref "R22") (pin "1") (pinfunction "1_1") (pintype "passive"))
      (node (ref "R38") (pin "2") (pinfunction "2_2") (pintype "passive"))
    )
    (net (code "33") (name "Net-(PCB1-PadP9.26)") (class "Default")
      (node (ref "PCB1") (pin "P9.26") (pinfunction "P9.26_P9.26") (pintype "bidirectional"))
      (node (ref "R21") (pin "1") (pinfunction "1_1") (pintype "passive"))
      (node (ref "R36") (pin "2") (pinfunction "2_2") (pintype "passive"))
    )
    (net (code "34") (name "Net-(PCB1-PadP9.43)") (class "Default")
      (node (ref "PCB1") (pin "P9.43") (pinfunction "P9.43_P9.43") (pintype "bidirectional"))
      (node (ref "R40") (pin "2") (pinfunction "2_2") (pintype "passive"))
    )
    (net (code "35") (name "Net-(Q2-G)") (class "Default")
      (node (ref "C10") (pin "1") (pinfunction "1_1") (pintype "passive"))
      (node (ref "Q2") (pin "1") (pinfunction "G_1") (pintype "passive"))
      (node (ref "R8") (pin "1") (pinfunction "1_1") (pintype "passive"))
    )
    (net (code "36") (name "Net-(Q3-G)") (class "Default")
      (node (ref "C11") (pin "1") (pinfunction "1_1") (pintype "passive"))
      (node (ref "Q3") (pin "1") (pinfunction "G_1") (pintype "passive"))
      (node (ref "R9") (pin "1") (pinfunction "1_1") (pintype "passive"))
    )
    (net (code "37") (name "Net-(Q4-G)") (class "Default")
      (node (ref "C12") (pin "1") (pinfunction "1_1") (pintype "passive"))
      (node (ref "Q4") (pin "1") (pinfunction "G_1") (pintype "passive"))
      (node (ref "R10") (pin "1") (pinfunction "1_1") (pintype "passive"))
    )
    (net (code "38") (name "Net-(Q5-G)") (class "Default")
      (node (ref "C13") (pin "1") (pinfunction "1_1") (pintype "passive"))
      (node (ref "Q5") (pin "1") (pinfunction "G_1") (pintype "passive"))
      (node (ref "R11") (pin "1") (pinfunction "1_1") (pintype "passive"))
    )
    (net (code "39") (name "Net-(Q6-S)") (class "Default")
      (node (ref "Q6") (pin "2") (pinfunction "S_2") (pintype "passive"))
      (node (ref "Q7") (pin "P$4") (pinfunction "G_P$4") (pintype "bidirectional"))
      (node (ref "R19") (pin "2") (pinfunction "2_2") (pintype "passive"))
      (node (ref "R20") (pin "1") (pinfunction "1_1") (pintype "passive"))
    )
    (net (code "40") (name "Net-(Q8-G)") (class "Default")
      (node (ref "Q8") (pin "P$4") (pinfunction "G_P$4") (pintype "bidirectional"))
      (node (ref "U1") (pin "27") (pinfunction "HIDRV_27") (pintype "bidirectional"))
    )
    (net (code "41") (name "Net-(Q9-G)") (class "Default")
      (node (ref "Q9") (pin "P$4") (pinfunction "G_P$4") (pintype "bidirectional"))
      (node (ref "U1") (pin "25") (pinfunction "LODRV_25") (pintype "bidirectional"))
    )
    (net (code "42") (name "Net-(Q12-D-PadP$5)") (class "Default")
      (node (ref "Q12") (pin "P$5") (pinfunction "D_P$5") (pintype "bidirectional"))
      (node (ref "Q12") (pin "P$6") (pinfunction "D_P$6") (pintype "bidirectional"))
      (node (ref "Q12") (pin "P$7") (pinfunction "D_P$7") (pintype "bidirectional"))
      (node (ref "Q12") (pin "P$8") (pinfunction "D_P$8") (pintype "bidirectional"))
      (node (ref "Q12") (pin "PAD") (pinfunction "D_PAD") (pintype "bidirectional"))
      (node (ref "Q13") (pin "P$5") (pinfunction "D_P$5") (pintype "bidirectional"))
      (node (ref "Q13") (pin "P$6") (pinfunction "D_P$6") (pintype "bidirectional"))
      (node (ref "Q13") (pin "P$7") (pinfunction "D_P$7") (pintype "bidirectional"))
      (node (ref "Q13") (pin "P$8") (pinfunction "D_P$8") (pintype "bidirectional"))
      (node (ref "Q13") (pin "PAD") (pinfunction "D_PAD") (pintype "bidirectional"))
    )
    (net (code "43") (name "Net-(Q12-G)") (class "Default")
      (node (ref "Q12") (pin "P$4") (pinfunction "G_P$4") (pintype "bidirectional"))
      (node (ref "R27") (pin "2") (pinfunction "2_2") (pintype "passive"))
      (node (ref "R29") (pin "1") (pinfunction "1_1") (pintype "passive"))
    )
    (net (code "44") (name "Net-(Q13-G)") (class "Default")
      (node (ref "Q13") (pin "P$4") (pinfunction "G_P$4") (pintype "bidirectional"))
      (node (ref "R28") (pin "2") (pinfunction "2_2") (pintype "passive"))
      (node (ref "R30") (pin "1") (pinfunction "1_1") (pintype "passive"))
    )
    (net (code "45") (name "Net-(Q14-G)") (class "Default")
      (node (ref "Q14") (pin "P$4") (pinfunction "G_P$4") (pintype "bidirectional"))
      (node (ref "U2") (pin "7") (pinfunction "HDRV_7") (pintype "passive"))
    )
    (net (code "46") (name "Net-(Q15-G)") (class "Default")
      (node (ref "Q15") (pin "P$4") (pinfunction "G_P$4") (pintype "bidirectional"))
      (node (ref "R44") (pin "1") (pinfunction "1_1") (pintype "passive"))
      (node (ref "U2") (pin "9") (pinfunction "LDRV/OC_9") (pintype "passive"))
    )
    (net (code "47") (name "Net-(U1-ACFET)") (class "Default")
      (node (ref "R19") (pin "1") (pinfunction "1_1") (pintype "passive"))
      (node (ref "U1") (pin "29") (pinfunction "ACFET_29") (pintype "bidirectional"))
    )
    (net (code "48") (name "Net-(U1-ACP)") (class "Default")
      (node (ref "R16") (pin "1") (pinfunction "1_1") (pintype "passive"))
      (node (ref "U1") (pin "31") (pinfunction "ACP_31") (pintype "bidirectional"))
    )
    (net (code "49") (name "Net-(U1-AFEFUSE)") (class "Default")
      (node (ref "R5") (pin "2") (pinfunction "2_2") (pintype "passive"))
      (node (ref "U1") (pin "21") (pinfunction "AFEFUSE_21") (pintype "bidirectional"))
    )
    (net (code "50") (name "Net-(U1-CHG)") (class "Default")
      (node (ref "R27") (pin "1") (pinfunction "1_1") (pintype "passive"))
      (node (ref "U1") (pin "32") (pinfunction "CHG_32") (pintype "bidirectional"))
    )
    (net (code "51") (name "Net-(U1-DSG)") (class "Default")
      (node (ref "R28") (pin "1") (pinfunction "1_1") (pintype "passive"))
      (node (ref "U1") (pin "30") (pinfunction "DSG_30") (pintype "bidirectional"))
    )
    (net (code "52") (name "Net-(U1-GPIO0)") (class "Default")
      (node (ref "R39") (pin "1") (pinfunction "1_1") (pintype "passive"))
      (node (ref "U1") (pin "14") (pinfunction "GPIO0_14") (pintype "bidirectional"))
    )
    (net (code "53") (name "Net-(U1-HSRN)") (class "Default")
      (node (ref "C22") (pin "2") (pinfunction "2_2") (pintype "passive"))
      (node (ref "C24") (pin "1") (pinfunction "1_1") (pintype "passive"))
      (node (ref "R31") (pin "P$4") (pinfunction "P$4_P$4") (pintype "bidirectional"))
      (node (ref "U1") (pin "19") (pinfunction "HSRN_19") (pintype "bidirectional"))
    )
    (net (code "54") (name "Net-(U1-HSRP)") (class "Default")
      (node (ref "C22") (pin "1") (pinfunction "1_1") (pintype "passive"))
      (node (ref "C23") (pin "1") (pinfunction "1_1") (pintype "passive"))
      (node (ref "R31") (pin "P$3") (pinfunction "P$3_P$3") (pintype "bidirectional"))
      (node (ref "U1") (pin "20") (pinfunction "HSRP_20") (pintype "bidirectional"))
    )
    (net (code "55") (name "Net-(U1-PBI)") (class "Default")
      (node (ref "C8") (pin "1") (pinfunction "1_1") (pintype "passive"))
      (node (ref "U1") (pin "2") (pinfunction "PBI_2") (pintype "bidirectional"))
    )
    (net (code "56") (name "Net-(U1-PH)") (class "Default")
      (node (ref "C21") (pin "2") (pinfunction "2_2") (pintype "passive"))
      (node (ref "L1") (pin "P$1") (pinfunction "P$1_P$1") (pintype "bidirectional"))
      (node (ref "Q8") (pin "P$1") (pinfunction "S_P$1") (pintype "bidirectional"))
      (node (ref "Q8") (pin "P$2") (pinfunction "S_P$2") (pintype "bidirectional"))
      (node (ref "Q8") (pin "P$3") (pinfunction "S_P$3") (pintype "bidirectional"))
      (node (ref "Q9") (pin "P$5") (pinfunction "D_P$5") (pintype "bidirectional"))
      (node (ref "Q9") (pin "P$6") (pinfunction "D_P$6") (pintype "bidirectional"))
      (node (ref "Q9") (pin "P$7") (pinfunction "D_P$7") (pintype "bidirectional"))
      (node (ref "Q9") (pin "P$8") (pinfunction "D_P$8") (pintype "bidirectional"))
      (node (ref "Q9") (pin "PAD") (pinfunction "D_PAD") (pintype "bidirectional"))
      (node (ref "U1") (pin "26") (pinfunction "PH_26") (pintype "bidirectional"))
    )
    (net (code "57") (name "Net-(U1-REGN)") (class "Default")
      (node (ref "C20") (pin "1") (pinfunction "1_1") (pintype "passive"))
      (node (ref "D2") (pin "1") (pinfunction "A_1") (pintype "passive"))
      (node (ref "D2") (pin "2") (pinfunction "A_2") (pintype "passive"))
      (node (ref "U1") (pin "23") (pinfunction "REGN_23") (pintype "bidirectional"))
    )
    (net (code "58") (name "Net-(U1-SMBC)") (class "Default")
      (node (ref "R37") (pin "1") (pinfunction "1_1") (pintype "passive"))
      (node (ref "U1") (pin "17") (pinfunction "SMBC_17") (pintype "bidirectional"))
    )
    (net (code "59") (name "Net-(U1-SMBD)") (class "Default")
      (node (ref "R35") (pin "1") (pinfunction "1_1") (pintype "passive"))
      (node (ref "U1") (pin "16") (pinfunction "SMBD_16") (pintype "bidirectional"))
    )
    (net (code "60") (name "Net-(U1-SRN)") (class "Default")
      (node (ref "C5") (pin "2") (pinfunction "2_2") (pintype "passive"))
      (node (ref "C6") (pin "2") (pinfunction "2_2") (pintype "passive"))
      (node (ref "R32") (pin "P$3") (pinfunction "P$3_P$3") (pintype "bidirectional"))
      (node (ref "U1") (pin "7") (pinfunction "SRN_7") (pintype "bidirectional"))
    )
    (net (code "61") (name "Net-(U1-SRP)") (class "Default")
      (node (ref "C5") (pin "1") (pinfunction "1_1") (pintype "passive"))
      (node (ref "C6") (pin "1") (pinfunction "1_1") (pintype "passive"))
      (node (ref "R32") (pin "P$4") (pinfunction "P$4_P$4") (pintype "bidirectional"))
      (node (ref "U1") (pin "8") (pinfunction "SRP_8") (pintype "bidirectional"))
    )
    (net (code "62") (name "Net-(U1-TS1)") (class "Default")
      (node (ref "J3") (pin "1") (pinfunction "1_1") (pintype "bidirectional"))
      (node (ref "R8") (pin "2") (pinfunction "2_2") (pintype "passive"))
      (node (ref "U1") (pin "10") (pinfunction "TS1_10") (pintype "bidirectional"))
    )
    (net (code "63") (name "Net-(U1-TS2)") (class "Default")
      (node (ref "J3") (pin "3") (pinfunction "3_3") (pintype "bidirectional"))
      (node (ref "R9") (pin "2") (pinfunction "2_2") (pintype "passive"))
      (node (ref "U1") (pin "11") (pinfunction "TS2_11") (pintype "bidirectional"))
    )
    (net (code "64") (name "Net-(U1-TS3)") (class "Default")
      (node (ref "J3") (pin "5") (pinfunction "5_5") (pintype "bidirectional"))
      (node (ref "R10") (pin "2") (pinfunction "2_2") (pintype "passive"))
      (node (ref "U1") (pin "12") (pinfunction "TS3_12") (pintype "bidirectional"))
    )
    (net (code "65") (name "Net-(U1-TS4)") (class "Default")
      (node (ref "J3") (pin "7") (pinfunction "7_7") (pintype "bidirectional"))
      (node (ref "R11") (pin "2") (pinfunction "2_2") (pintype "passive"))
      (node (ref "U1") (pin "13") (pinfunction "TS4_13") (pintype "bidirectional"))
    )
    (net (code "66") (name "Net-(U1-VC1)") (class "Default")
      (node (ref "C3") (pin "2") (pinfunction "2_2") (pintype "passive"))
      (node (ref "C4") (pin "1") (pinfunction "1_1") (pintype "passive"))
      (node (ref "R4") (pin "2") (pinfunction "2_2") (pintype "passive"))
      (node (ref "U1") (pin "6") (pinfunction "VC1_6") (pintype "bidirectional"))
    )
    (net (code "67") (name "Net-(U1-VC2)") (class "Default")
      (node (ref "C2") (pin "2") (pinfunction "2_2") (pintype "passive"))
      (node (ref "C3") (pin "1") (pinfunction "1_1") (pintype "passive"))
      (node (ref "R3") (pin "2") (pinfunction "2_2") (pintype "passive"))
      (node (ref "U1") (pin "5") (pinfunction "VC2_5") (pintype "bidirectional"))
    )
    (net (code "68") (name "Net-(U1-VC3)") (class "Default")
      (node (ref "C1") (pin "2") (pinfunction "2_2") (pintype "passive"))
      (node (ref "C2") (pin "1") (pinfunction "1_1") (pintype "passive"))
      (node (ref "R2") (pin "2") (pinfunction "2_2") (pintype "passive"))
      (node (ref "U1") (pin "4") (pinfunction "VC3_4") (pintype "bidirectional"))
    )
    (net (code "69") (name "Net-(U1-VC4)") (class "Default")
      (node (ref "C1") (pin "1") (pinfunction "1_1") (pintype "passive"))
      (node (ref "R1") (pin "2") (pinfunction "2_2") (pintype "passive"))
      (node (ref "U1") (pin "3") (pinfunction "VC4_3") (pintype "bidirectional"))
    )
    (net (code "70") (name "Net-(U1-VCC)") (class "Default")
      (node (ref "C17") (pin "1") (pinfunction "1_1") (pintype "passive"))
      (node (ref "R23") (pin "1") (pinfunction "1_1") (pintype "passive"))
      (node (ref "U1") (pin "22") (pinfunction "VCC_22") (pintype "bidirectional"))
    )
    (net (code "71") (name "Net-(U1-VFB)") (class "Default")
      (node (ref "C27") (pin "2") (pinfunction "2_2") (pintype "passive"))
      (node (ref "R33") (pin "1") (pinfunction "1_1") (pintype "passive"))
      (node (ref "R34") (pin "2") (pinfunction "2_2") (pintype "passive"))
      (node (ref "U1") (pin "18") (pinfunction "VFB_18") (pintype "bidirectional"))
    )
    (net (code "72") (name "Net-(U2-BOOT)") (class "Default")
      (node (ref "C34") (pin "1") (pinfunction "1_1") (pintype "passive"))
      (node (ref "U2") (pin "6") (pinfunction "BOOT_6") (pintype "passive"))
    )
    (net (code "73") (name "Net-(U2-BP)") (class "Default")
      (node (ref "C33") (pin "1") (pinfunction "1_1") (pintype "passive"))
      (node (ref "R13") (pin "2") (pinfunction "2_2") (pintype "passive"))
      (node (ref "U2") (pin "10") (pinfunction "BP_10") (pintype "passive"))
    )
    (net (code "74") (name "Net-(U2-COMP)") (class "Default")
      (node (ref "C31") (pin "1") (pinfunction "1_1") (pintype "passive"))
      (node (ref "C32") (pin "1") (pinfunction "1_1") (pintype "passive"))
      (node (ref "U2") (pin "4") (pinfunction "COMP_4") (pintype "passive"))
    )
    (net (code "75") (name "Net-(U2-EN{slash}SS)") (class "Default")
      (node (ref "C30") (pin "1") (pinfunction "1_1") (pintype "passive"))
      (node (ref "U2") (pin "2") (pinfunction "EN/SS_2") (pintype "passive"))
    )
    (net (code "76") (name "Net-(U2-FB)") (class "Default")
      (node (ref "C31") (pin "2") (pinfunction "2_2") (pintype "passive"))
      (node (ref "C35") (pin "2") (pinfunction "2_2") (pintype "passive"))
      (node (ref "R12") (pin "1") (pinfunction "1_1") (pintype "passive"))
      (node (ref "R15") (pin "1") (pinfunction "1_1") (pintype "passive"))
      (node (ref "R43") (pin "2") (pinfunction "2_2") (pintype "passive"))
      (node (ref "U2") (pin "5") (pinfunction "FB_5") (pintype "passive"))
    )
    (net (code "77") (name "Net-(U2-PGOOD)") (class "Default")
      (node (ref "R13") (pin "1") (pinfunction "1_1") (pintype "passive"))
      (node (ref "U2") (pin "3") (pinfunction "PGOOD_3") (pintype "passive"))
    )
    (net (code "78") (name "Net-(U2-SW)") (class "Default")
      (node (ref "C34") (pin "2") (pinfunction "2_2") (pintype "passive"))
      (node (ref "L2") (pin "P$1") (pinfunction "P$1_P$1") (pintype "bidirectional"))
      (node (ref "Q14") (pin "P$1") (pinfunction "S_P$1") (pintype "bidirectional"))
      (node (ref "Q14") (pin "P$2") (pinfunction "S_P$2") (pintype "bidirectional"))
      (node (ref "Q14") (pin "P$3") (pinfunction "S_P$3") (pintype "bidirectional"))
      (node (ref "Q15") (pin "P$5") (pinfunction "D_P$5") (pintype "bidirectional"))
      (node (ref "Q15") (pin "P$6") (pinfunction "D_P$6") (pintype "bidirectional"))
      (node (ref "Q15") (pin "P$7") (pinfunction "D_P$7") (pintype "bidirectional"))
      (node (ref "Q15") (pin "P$8") (pinfunction "D_P$8") (pintype "bidirectional"))
      (node (ref "Q15") (pin "PAD") (pinfunction "D_PAD") (pintype "bidirectional"))
      (node (ref "U2") (pin "8") (pinfunction "SW_8") (pintype "passive"))
    )
    (net (code "79") (name "unconnected-(PCB1-PadP8.1)") (class "Default")
      (node (ref "PCB1") (pin "P8.1") (pinfunction "P8.1_P8.1") (pintype "bidirectional"))
    )
    (net (code "80") (name "unconnected-(PCB1-PadP8.2)") (class "Default")
      (node (ref "PCB1") (pin "P8.2") (pinfunction "P8.2_P8.2") (pintype "bidirectional"))
    )
    (net (code "81") (name "unconnected-(PCB1-PadP8.3)") (class "Default")
      (node (ref "PCB1") (pin "P8.3") (pinfunction "P8.3_P8.3") (pintype "bidirectional"))
    )
    (net (code "82") (name "unconnected-(PCB1-PadP8.4)") (class "Default")
      (node (ref "PCB1") (pin "P8.4") (pinfunction "P8.4_P8.4") (pintype "bidirectional"))
    )
    (net (code "83") (name "unconnected-(PCB1-PadP8.5)") (class "Default")
      (node (ref "PCB1") (pin "P8.5") (pinfunction "P8.5_P8.5") (pintype "bidirectional"))
    )
    (net (code "84") (name "unconnected-(PCB1-PadP8.6)") (class "Default")
      (node (ref "PCB1") (pin "P8.6") (pinfunction "P8.6_P8.6") (pintype "bidirectional"))
    )
    (net (code "85") (name "unconnected-(PCB1-PadP8.7)") (class "Default")
      (node (ref "PCB1") (pin "P8.7") (pinfunction "P8.7_P8.7") (pintype "bidirectional"))
    )
    (net (code "86") (name "unconnected-(PCB1-PadP8.8)") (class "Default")
      (node (ref "PCB1") (pin "P8.8") (pinfunction "P8.8_P8.8") (pintype "bidirectional"))
    )
    (net (code "87") (name "unconnected-(PCB1-PadP8.9)") (class "Default")
      (node (ref "PCB1") (pin "P8.9") (pinfunction "P8.9_P8.9") (pintype "bidirectional"))
    )
    (net (code "88") (name "unconnected-(PCB1-PadP8.10)") (class "Default")
      (node (ref "PCB1") (pin "P8.10") (pinfunction "P8.10_P8.10") (pintype "bidirectional"))
    )
    (net (code "89") (name "unconnected-(PCB1-PadP8.11)") (class "Default")
      (node (ref "PCB1") (pin "P8.11") (pinfunction "P8.11_P8.11") (pintype "bidirectional"))
    )
    (net (code "90") (name "unconnected-(PCB1-PadP8.12)") (class "Default")
      (node (ref "PCB1") (pin "P8.12") (pinfunction "P8.12_P8.12") (pintype "bidirectional"))
    )
    (net (code "91") (name "unconnected-(PCB1-PadP8.13)") (class "Default")
      (node (ref "PCB1") (pin "P8.13") (pinfunction "P8.13_P8.13") (pintype "bidirectional"))
    )
    (net (code "92") (name "unconnected-(PCB1-PadP8.14)") (class "Default")
      (node (ref "PCB1") (pin "P8.14") (pinfunction "P8.14_P8.14") (pintype "bidirectional"))
    )
    (net (code "93") (name "unconnected-(PCB1-PadP8.15)") (class "Default")
      (node (ref "PCB1") (pin "P8.15") (pinfunction "P8.15_P8.15") (pintype "bidirectional"))
    )
    (net (code "94") (name "unconnected-(PCB1-PadP8.16)") (class "Default")
      (node (ref "PCB1") (pin "P8.16") (pinfunction "P8.16_P8.16") (pintype "bidirectional"))
    )
    (net (code "95") (name "unconnected-(PCB1-PadP8.17)") (class "Default")
      (node (ref "PCB1") (pin "P8.17") (pinfunction "P8.17_P8.17") (pintype "bidirectional"))
    )
    (net (code "96") (name "unconnected-(PCB1-PadP8.18)") (class "Default")
      (node (ref "PCB1") (pin "P8.18") (pinfunction "P8.18_P8.18") (pintype "bidirectional"))
    )
    (net (code "97") (name "unconnected-(PCB1-PadP8.19)") (class "Default")
      (node (ref "PCB1") (pin "P8.19") (pinfunction "P8.19_P8.19") (pintype "bidirectional"))
    )
    (net (code "98") (name "unconnected-(PCB1-PadP8.20)") (class "Default")
      (node (ref "PCB1") (pin "P8.20") (pinfunction "P8.20_P8.20") (pintype "bidirectional"))
    )
    (net (code "99") (name "unconnected-(PCB1-PadP8.21)") (class "Default")
      (node (ref "PCB1") (pin "P8.21") (pinfunction "P8.21_P8.21") (pintype "bidirectional"))
    )
    (net (code "100") (name "unconnected-(PCB1-PadP8.22)") (class "Default")
      (node (ref "PCB1") (pin "P8.22") (pinfunction "P8.22_P8.22") (pintype "bidirectional"))
    )
    (net (code "101") (name "unconnected-(PCB1-PadP8.23)") (class "Default")
      (node (ref "PCB1") (pin "P8.23") (pinfunction "P8.23_P8.23") (pintype "bidirectional"))
    )
    (net (code "102") (name "unconnected-(PCB1-PadP8.24)") (class "Default")
      (node (ref "PCB1") (pin "P8.24") (pinfunction "P8.24_P8.24") (pintype "bidirectional"))
    )
    (net (code "103") (name "unconnected-(PCB1-PadP8.25)") (class "Default")
      (node (ref "PCB1") (pin "P8.25") (pinfunction "P8.25_P8.25") (pintype "bidirectional"))
    )
    (net (code "104") (name "unconnected-(PCB1-PadP8.26)") (class "Default")
      (node (ref "PCB1") (pin "P8.26") (pinfunction "P8.26_P8.26") (pintype "bidirectional"))
    )
    (net (code "105") (name "unconnected-(PCB1-PadP8.27)") (class "Default")
      (node (ref "PCB1") (pin "P8.27") (pinfunction "P8.27_P8.27") (pintype "bidirectional"))
    )
    (net (code "106") (name "unconnected-(PCB1-PadP8.28)") (class "Default")
      (node (ref "PCB1") (pin "P8.28") (pinfunction "P8.28_P8.28") (pintype "bidirectional"))
    )
    (net (code "107") (name "unconnected-(PCB1-PadP8.29)") (class "Default")
      (node (ref "PCB1") (pin "P8.29") (pinfunction "P8.29_P8.29") (pintype "bidirectional"))
    )
    (net (code "108") (name "unconnected-(PCB1-PadP8.30)") (class "Default")
      (node (ref "PCB1") (pin "P8.30") (pinfunction "P8.30_P8.30") (pintype "bidirectional"))
    )
    (net (code "109") (name "unconnected-(PCB1-PadP8.31)") (class "Default")
      (node (ref "PCB1") (pin "P8.31") (pinfunction "P8.31_P8.31") (pintype "bidirectional"))
    )
    (net (code "110") (name "unconnected-(PCB1-PadP8.32)") (class "Default")
      (node (ref "PCB1") (pin "P8.32") (pinfunction "P8.32_P8.32") (pintype "bidirectional"))
    )
    (net (code "111") (name "unconnected-(PCB1-PadP8.33)") (class "Default")
      (node (ref "PCB1") (pin "P8.33") (pinfunction "P8.33_P8.33") (pintype "bidirectional"))
    )
    (net (code "112") (name "unconnected-(PCB1-PadP8.34)") (class "Default")
      (node (ref "PCB1") (pin "P8.34") (pinfunction "P8.34_P8.34") (pintype "bidirectional"))
    )
    (net (code "113") (name "unconnected-(PCB1-PadP8.35)") (class "Default")
      (node (ref "PCB1") (pin "P8.35") (pinfunction "P8.35_P8.35") (pintype "bidirectional"))
    )
    (net (code "114") (name "unconnected-(PCB1-PadP8.36)") (class "Default")
      (node (ref "PCB1") (pin "P8.36") (pinfunction "P8.36_P8.36") (pintype "bidirectional"))
    )
    (net (code "115") (name "unconnected-(PCB1-PadP8.37)") (class "Default")
      (node (ref "PCB1") (pin "P8.37") (pinfunction "P8.37_P8.37") (pintype "bidirectional"))
    )
    (net (code "116") (name "unconnected-(PCB1-PadP8.38)") (class "Default")
      (node (ref "PCB1") (pin "P8.38") (pinfunction "P8.38_P8.38") (pintype "bidirectional"))
    )
    (net (code "117") (name "unconnected-(PCB1-PadP8.39)") (class "Default")
      (node (ref "PCB1") (pin "P8.39") (pinfunction "P8.39_P8.39") (pintype "bidirectional"))
    )
    (net (code "118") (name "unconnected-(PCB1-PadP8.40)") (class "Default")
      (node (ref "PCB1") (pin "P8.40") (pinfunction "P8.40_P8.40") (pintype "bidirectional"))
    )
    (net (code "119") (name "unconnected-(PCB1-PadP8.41)") (class "Default")
      (node (ref "PCB1") (pin "P8.41") (pinfunction "P8.41_P8.41") (pintype "bidirectional"))
    )
    (net (code "120") (name "unconnected-(PCB1-PadP8.42)") (class "Default")
      (node (ref "PCB1") (pin "P8.42") (pinfunction "P8.42_P8.42") (pintype "bidirectional"))
    )
    (net (code "121") (name "unconnected-(PCB1-PadP8.43)") (class "Default")
      (node (ref "PCB1") (pin "P8.43") (pinfunction "P8.43_P8.43") (pintype "bidirectional"))
    )
    (net (code "122") (name "unconnected-(PCB1-PadP8.44)") (class "Default")
      (node (ref "PCB1") (pin "P8.44") (pinfunction "P8.44_P8.44") (pintype "bidirectional"))
    )
    (net (code "123") (name "unconnected-(PCB1-PadP8.45)") (class "Default")
      (node (ref "PCB1") (pin "P8.45") (pinfunction "P8.45_P8.45") (pintype "bidirectional"))
    )
    (net (code "124") (name "unconnected-(PCB1-PadP8.46)") (class "Default")
      (node (ref "PCB1") (pin "P8.46") (pinfunction "P8.46_P8.46") (pintype "bidirectional"))
    )
    (net (code "125") (name "unconnected-(PCB1-PadP9.7)") (class "Default")
      (node (ref "PCB1") (pin "P9.7") (pinfunction "P9.7_P9.7") (pintype "bidirectional"))
    )
    (net (code "126") (name "unconnected-(PCB1-PadP9.8)") (class "Default")
      (node (ref "PCB1") (pin "P9.8") (pinfunction "P9.8_P9.8") (pintype "bidirectional"))
    )
    (net (code "127") (name "unconnected-(PCB1-PadP9.10)") (class "Default")
      (node (ref "PCB1") (pin "P9.10") (pinfunction "P9.10_P9.10") (pintype "bidirectional"))
    )
    (net (code "128") (name "unconnected-(PCB1-PadP9.11)") (class "Default")
      (node (ref "PCB1") (pin "P9.11") (pinfunction "P9.11_P9.11") (pintype "bidirectional"))
    )
    (net (code "129") (name "unconnected-(PCB1-PadP9.12)") (class "Default")
      (node (ref "PCB1") (pin "P9.12") (pinfunction "P9.12_P9.12") (pintype "bidirectional"))
    )
    (net (code "130") (name "unconnected-(PCB1-PadP9.13)") (class "Default")
      (node (ref "PCB1") (pin "P9.13") (pinfunction "P9.13_P9.13") (pintype "bidirectional"))
    )
    (net (code "131") (name "unconnected-(PCB1-PadP9.14)") (class "Default")
      (node (ref "PCB1") (pin "P9.14") (pinfunction "P9.14_P9.14") (pintype "bidirectional"))
    )
    (net (code "132") (name "unconnected-(PCB1-PadP9.15)") (class "Default")
      (node (ref "PCB1") (pin "P9.15") (pinfunction "P9.15_P9.15") (pintype "bidirectional"))
    )
    (net (code "133") (name "unconnected-(PCB1-PadP9.16)") (class "Default")
      (node (ref "PCB1") (pin "P9.16") (pinfunction "P9.16_P9.16") (pintype "bidirectional"))
    )
    (net (code "134") (name "unconnected-(PCB1-PadP9.17)") (class "Default")
      (node (ref "PCB1") (pin "P9.17") (pinfunction "P9.17_P9.17") (pintype "bidirectional"))
    )
    (net (code "135") (name "unconnected-(PCB1-PadP9.18)") (class "Default")
      (node (ref "PCB1") (pin "P9.18") (pinfunction "P9.18_P9.18") (pintype "bidirectional"))
    )
    (net (code "136") (name "unconnected-(PCB1-PadP9.19)") (class "Default")
      (node (ref "PCB1") (pin "P9.19") (pinfunction "P9.19_P9.19") (pintype "bidirectional"))
    )
    (net (code "137") (name "unconnected-(PCB1-PadP9.20)") (class "Default")
      (node (ref "PCB1") (pin "P9.20") (pinfunction "P9.20_P9.20") (pintype "bidirectional"))
    )
    (net (code "138") (name "unconnected-(PCB1-PadP9.21)") (class "Default")
      (node (ref "PCB1") (pin "P9.21") (pinfunction "P9.21_P9.21") (pintype "bidirectional"))
    )
    (net (code "139") (name "unconnected-(PCB1-PadP9.22)") (class "Default")
      (node (ref "PCB1") (pin "P9.22") (pinfunction "P9.22_P9.22") (pintype "bidirectional"))
    )
    (net (code "140") (name "unconnected-(PCB1-PadP9.23)") (class "Default")
      (node (ref "PCB1") (pin "P9.23") (pinfunction "P9.23_P9.23") (pintype "bidirectional"))
    )
    (net (code "141") (name "unconnected-(PCB1-PadP9.25)") (class "Default")
      (node (ref "PCB1") (pin "P9.25") (pinfunction "P9.25_P9.25") (pintype "bidirectional"))
    )
    (net (code "142") (name "unconnected-(PCB1-PadP9.27)") (class "Default")
      (node (ref "PCB1") (pin "P9.27") (pinfunction "P9.27_P9.27") (pintype "bidirectional"))
    )
    (net (code "143") (name "unconnected-(PCB1-PadP9.28)") (class "Default")
      (node (ref "PCB1") (pin "P9.28") (pinfunction "P9.28_P9.28") (pintype "bidirectional"))
    )
    (net (code "144") (name "unconnected-(PCB1-PadP9.29)") (class "Default")
      (node (ref "PCB1") (pin "P9.29") (pinfunction "P9.29_P9.29") (pintype "bidirectional"))
    )
    (net (code "145") (name "unconnected-(PCB1-PadP9.30)") (class "Default")
      (node (ref "PCB1") (pin "P9.30") (pinfunction "P9.30_P9.30") (pintype "bidirectional"))
    )
    (net (code "146") (name "unconnected-(PCB1-PadP9.31)") (class "Default")
      (node (ref "PCB1") (pin "P9.31") (pinfunction "P9.31_P9.31") (pintype "bidirectional"))
    )
    (net (code "147") (name "unconnected-(PCB1-PadP9.32)") (class "Default")
      (node (ref "PCB1") (pin "P9.32") (pinfunction "P9.32_P9.32") (pintype "bidirectional"))
    )
    (net (code "148") (name "unconnected-(PCB1-PadP9.33)") (class "Default")
      (node (ref "PCB1") (pin "P9.33") (pinfunction "P9.33_P9.33") (pintype "bidirectional"))
    )
    (net (code "149") (name "unconnected-(PCB1-PadP9.34)") (class "Default")
      (node (ref "PCB1") (pin "P9.34") (pinfunction "P9.34_P9.34") (pintype "bidirectional"))
    )
    (net (code "150") (name "unconnected-(PCB1-PadP9.35)") (class "Default")
      (node (ref "PCB1") (pin "P9.35") (pinfunction "P9.35_P9.35") (pintype "bidirectional"))
    )
    (net (code "151") (name "unconnected-(PCB1-PadP9.36)") (class "Default")
      (node (ref "PCB1") (pin "P9.36") (pinfunction "P9.36_P9.36") (pintype "bidirectional"))
    )
    (net (code "152") (name "unconnected-(PCB1-PadP9.37)") (class "Default")
      (node (ref "PCB1") (pin "P9.37") (pinfunction "P9.37_P9.37") (pintype "bidirectional"))
    )
    (net (code "153") (name "unconnected-(PCB1-PadP9.38)") (class "Default")
      (node (ref "PCB1") (pin "P9.38") (pinfunction "P9.38_P9.38") (pintype "bidirectional"))
    )
    (net (code "154") (name "unconnected-(PCB1-PadP9.39)") (class "Default")
      (node (ref "PCB1") (pin "P9.39") (pinfunction "P9.39_P9.39") (pintype "bidirectional"))
    )
    (net (code "155") (name "unconnected-(PCB1-PadP9.40)") (class "Default")
      (node (ref "PCB1") (pin "P9.40") (pinfunction "P9.40_P9.40") (pintype "bidirectional"))
    )
    (net (code "156") (name "unconnected-(PCB1-PadP9.41)") (class "Default")
      (node (ref "PCB1") (pin "P9.41") (pinfunction "P9.41_P9.41") (pintype "bidirectional"))
    )
    (net (code "157") (name "unconnected-(PCB1-PadP9.42)") (class "Default")
      (node (ref "PCB1") (pin "P9.42") (pinfunction "P9.42_P9.42") (pintype "bidirectional"))
    )
  )
)
